# Finger_IMU_PCB.net
KiCad netlist of a schematic drawn in Altium Designer
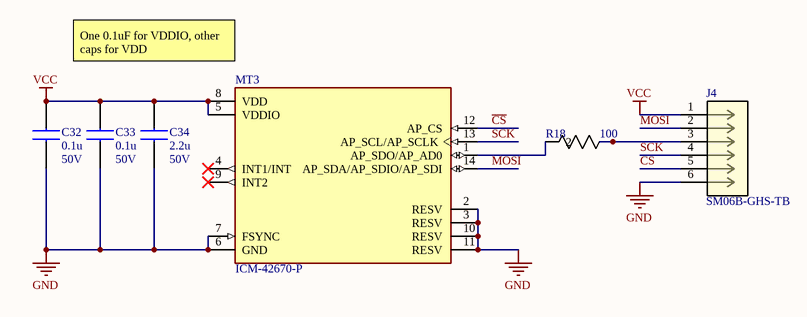
[diagram p0: Finger_IMU_PCB.SchDoc]

(export (version "E")
  (design (tool "Eeschema 10.0.6"))
  (components
    (comp (ref "C32")
      (value "0.1u")
      (footprint "CAPC2012X145N")
      (description "Multilayer Ceramic Chip Capacitors, Capacitance=0.1u")
      (fields
        (field (name "MANUFACTURER_PART_NUMBER") "KAM21BR71H104JM")
        (field (name "RATED VOLTAGE") "50V")
      )
      (libsource (lib "Caps") (part "KAM21BR71H104JM"))
    )
    (comp (ref "C33")
      (value "0.1u")
      (footprint "CAPC2012X145N")
      (description "Multilayer Ceramic Chip Capacitors, Capacitance=0.1u")
      (fields
        (field (name "MANUFACTURER_PART_NUMBER") "KAM21BR71H104JM")
        (field (name "RATED VOLTAGE") "50V")
      )
      (libsource (lib "Caps") (part "KAM21BR71H104JM"))
    )
    (comp (ref "C34")
      (value "2.2u")
      (footprint "CAPC2012X145N")
      (description "Multilayer Ceramic Chip Capacitors, Capacitance=2.2u")
      (fields
        (field (name "MANUFACTURER_PART_NUMBER") "C2012X7R1H225K125AE")
        (field (name "RATED VOLTAGE") "50V")
      )
      (libsource (lib "Caps") (part "C2012X7R1H225K125AE"))
    )
    (comp (ref "J4")
      (value "SM06B-GHS-TB")
      (footprint "CONN_SM06B-GHS-TB_JST")
      (description "No Description Available")
      (fields (field (name "COPYRIGHT") "Copyright (C) 2025 Ultra Librarian. All rights reserved."))
      (libsource (lib "SM06B-GHS-TB") (part "SM06B-GHS-TB"))
    )
    (comp (ref "MT3")
      (value "ICM-42670-P")
      (footprint "XDCR_ICM-42670-P")
      (libsource (lib "ICM-42670-P") (part "ICM-42670-P"))
    )
    (comp (ref "R18")
      (value "100")
      (footprint "RC0805N_YAG")
      (description "RES 0805 100 5% 1/8W")
      (fields (field (name "MANUFACTURER_PART_NUMBER") "RC0805JR-07100RL") (field (name "TOLERANCE") "5%"))
      (libsource (lib "Resistors") (part "RC0805JR-07100RL"))
    )
  )
  (nets
    (net (code "1") (name "/MOSI") (class "Default")
      (node (ref "J4") (pin "2") (pinfunction "2_2") (pintype "passive"))
      (node (ref "MT3") (pin "14") (pinfunction "AP_SDA/AP_SDIO/AP_SDI_14") (pintype "bidirectional"))
    )
    (net (code "2") (name "/SCK") (class "Default")
      (node (ref "J4") (pin "4") (pinfunction "4_4") (pintype "passive"))
      (node (ref "MT3") (pin "13") (pinfunction "AP_SCL/AP_SCLK_13") (pintype "input"))
    )
    (net (code "3") (name "/~{CS}") (class "Default")
      (node (ref "J4") (pin "5") (pinfunction "5_5") (pintype "passive"))
      (node (ref "MT3") (pin "12") (pinfunction "AP_CS_12") (pintype "input"))
    )
    (net (code "4") (name "GND") (class "Default")
      (node (ref "C32") (pin "1") (pinfunction "1_1") (pintype "passive"))
      (node (ref "C33") (pin "1") (pinfunction "1_1") (pintype "passive"))
      (node (ref "C34") (pin "1") (pinfunction "1_1") (pintype "passive"))
      (node (ref "J4") (pin "6") (pinfunction "6_6") (pintype "passive"))
      (node (ref "MT3") (pin "10") (pinfunction "RESV_10") (pintype "passive"))
      (node (ref "MT3") (pin "11") (pinfunction "RESV_11") (pintype "passive"))
      (node (ref "MT3") (pin "2") (pinfunction "RESV_2") (pintype "passive"))
      (node (ref "MT3") (pin "3") (pinfunction "RESV_3") (pintype "passive"))
      (node (ref "MT3") (pin "6") (pinfunction "GND_6") (pintype "power_in"))
      (node (ref "MT3") (pin "7") (pinfunction "FSYNC_7") (pintype "input"))
    )
    (net (code "5") (name "Net-(J4-Pad3)") (class "Default")
      (node (ref "J4") (pin "3") (pinfunction "3_3") (pintype "passive"))
      (node (ref "R18") (pin "1") (pinfunction "1_1") (pintype "passive"))
    )
    (net (code "6") (name "Net-(MT3-AP_SDO{slash}AP_AD0)") (class "Default")
      (node (ref "MT3") (pin "1") (pinfunction "AP_SDO/AP_AD0_1") (pintype "bidirectional"))
      (node (ref "R18") (pin "2") (pinfunction "2_2") (pintype "passive"))
    )
    (net (code "7") (name "VCC") (class "Default")
      (node (ref "C32") (pin "2") (pinfunction "2_2") (pintype "passive"))
      (node (ref "C33") (pin "2") (pinfunction "2_2") (pintype "passive"))
      (node (ref "C34") (pin "2") (pinfunction "2_2") (pintype "passive"))
      (node (ref "J4") (pin "1") (pinfunction "1_1") (pintype "passive"))
      (node (ref "MT3") (pin "5") (pinfunction "VDDIO_5") (pintype "power_in"))
      (node (ref "MT3") (pin "8") (pinfunction "VDD_8") (pintype "power_in"))
    )
    (net (code "8") (name "unconnected-(MT3-INT1{slash}INT-Pad4)") (class "Default")
      (node (ref "MT3") (pin "4") (pinfunction "INT1/INT_4") (pintype "output+no_connect"))
    )
    (net (code "9") (name "unconnected-(MT3-INT2-Pad9)") (class "Default")
      (node (ref "MT3") (pin "9") (pinfunction "INT2_9") (pintype "output+no_connect"))
    )
  )
)
